# Placa_principal.net
KiCad netlist of a schematic drawn in EAGLE
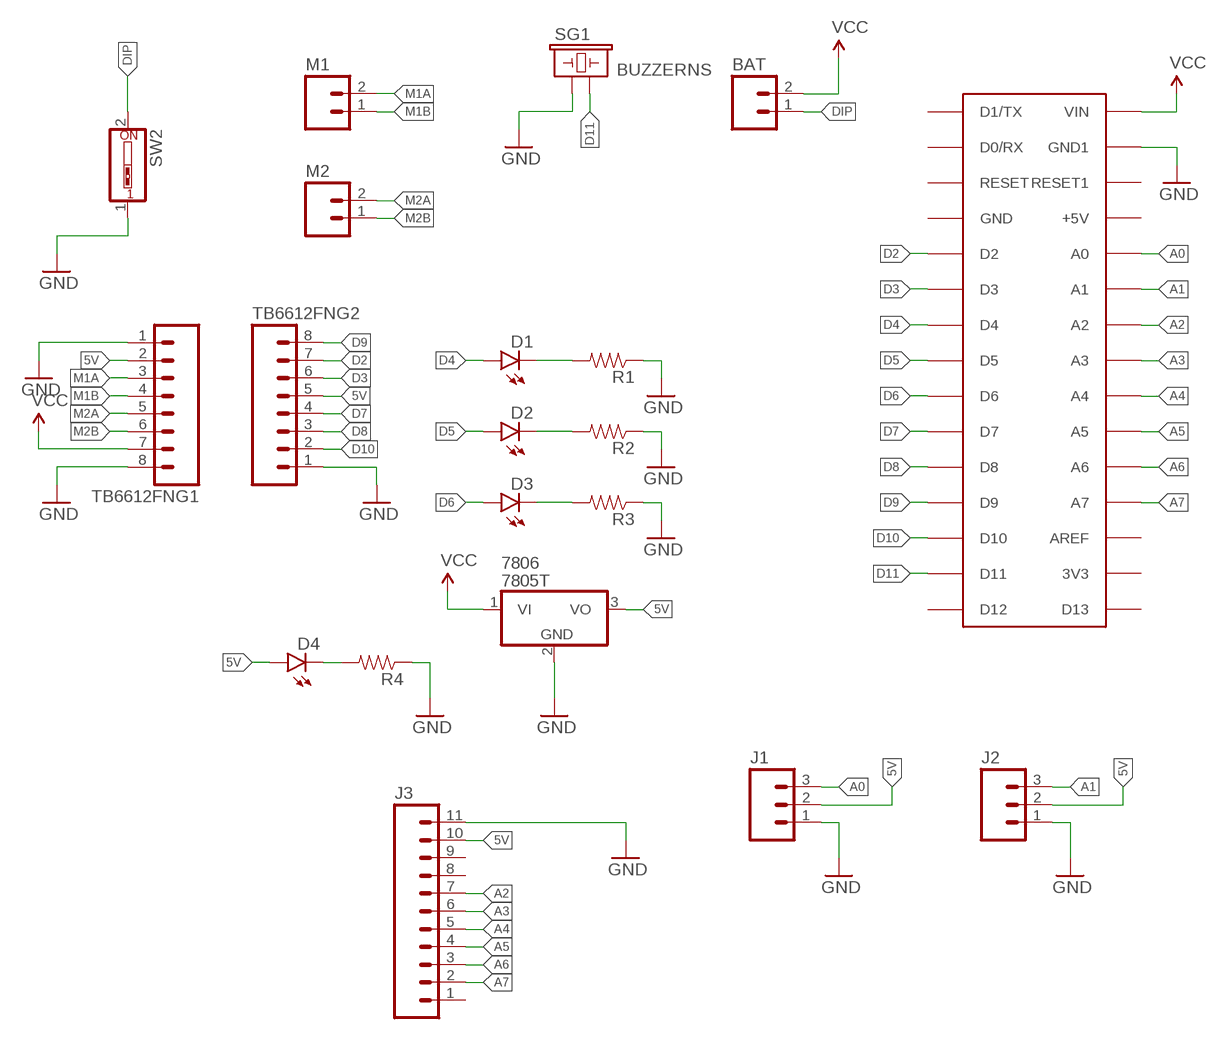
[diagram p0: schematic, sheet 1]

(export (version "E")
  (design (tool "Eeschema 10.0.6"))
  (components
    (comp (ref "7806")
      (value "7805T")
      (footprint "eagle-import:TO220H")
      (libsource (lib "eagle-import") (part "78T05"))
    )
    (comp (ref "BAT")
      (value "M02PTH")
      (footprint "eagle-import:1X02")
      (libsource (lib "eagle-import") (part "M02PTH"))
    )
    (comp (ref "D1")
      (value "LED5MM")
      (footprint "eagle-import:LED5MM")
      (libsource (lib "eagle-import") (part "LED5MM"))
    )
    (comp (ref "D2")
      (value "LED5MM")
      (footprint "eagle-import:LED5MM")
      (libsource (lib "eagle-import") (part "LED5MM"))
    )
    (comp (ref "D3")
      (value "LED5MM")
      (footprint "eagle-import:LED5MM")
      (libsource (lib "eagle-import") (part "LED5MM"))
    )
    (comp (ref "D4")
      (value "LED5MM")
      (footprint "eagle-import:LED5MM")
      (libsource (lib "eagle-import") (part "LED5MM"))
    )
    (comp (ref "J1")
      (value "M03PTH")
      (footprint "eagle-import:1X03")
      (libsource (lib "eagle-import") (part "M03PTH"))
    )
    (comp (ref "J2")
      (value "M03PTH")
      (footprint "eagle-import:1X03")
      (libsource (lib "eagle-import") (part "M03PTH"))
    )
    (comp (ref "J3")
      (value "M11PTH")
      (footprint "eagle-import:1X11")
      (libsource (lib "eagle-import") (part "M11PTH"))
    )
    (comp (ref "M1")
      (value "M02JST-PTH-VERT")
      (footprint "eagle-import:JST-2-PTH-VERT")
      (libsource (lib "eagle-import") (part "M02JST-PTH-VERT"))
    )
    (comp (ref "M2")
      (value "M02JST-PTH-VERT")
      (footprint "eagle-import:JST-2-PTH-VERT")
      (libsource (lib "eagle-import") (part "M02JST-PTH-VERT"))
    )
    (comp (ref "R1")
      (value "RESISTOREZ")
      (footprint "eagle-import:AXIAL-0.3EZ")
      (libsource (lib "eagle-import") (part "RESISTOREZ"))
    )
    (comp (ref "R2")
      (value "RESISTOREZ")
      (footprint "eagle-import:AXIAL-0.3EZ")
      (libsource (lib "eagle-import") (part "RESISTOREZ"))
    )
    (comp (ref "R3")
      (value "RESISTOREZ")
      (footprint "eagle-import:AXIAL-0.3EZ")
      (libsource (lib "eagle-import") (part "RESISTOREZ"))
    )
    (comp (ref "R4")
      (value "RESISTOREZ")
      (footprint "eagle-import:AXIAL-0.3EZ")
      (libsource (lib "eagle-import") (part "RESISTOREZ"))
    )
    (comp (ref "SG1")
      (value "BUZZERNS")
      (footprint "eagle-import:BUZZER-12MM-NS")
      (libsource (lib "eagle-import") (part "BUZZERNS"))
    )
    (comp (ref "SW2")
      (value "SW_DIP-1")
      (footprint "eagle-import:EDG-01")
      (libsource (lib "eagle-import") (part "SW_DIP-1"))
    )
    (comp (ref "TB6612FNG1")
      (value "M08")
      (footprint "eagle-import:1X08_ROUND")
      (libsource (lib "eagle-import") (part "M08"))
    )
    (comp (ref "TB6612FNG2")
      (value "M08")
      (footprint "eagle-import:1X08_ROUND")
      (libsource (lib "eagle-import") (part "M08"))
    )
    (comp (ref "U$2")
      (value "ARDUINONANO")
      (footprint "eagle-import:PDIP-32")
      (libsource (lib "eagle-import") (part "ARDUINONANO"))
    )
  )
  (nets
    (net (code "1") (name "5V") (class "Default")
      (node (ref "7806") (pin "3") (pinfunction "VO_3") (pintype "passive"))
      (node (ref "D4") (pin "A") (pinfunction "A_A") (pintype "passive"))
      (node (ref "J1") (pin "2") (pinfunction "2_2") (pintype "passive"))
      (node (ref "J2") (pin "2") (pinfunction "2_2") (pintype "passive"))
      (node (ref "J3") (pin "10") (pinfunction "10_10") (pintype "passive"))
      (node (ref "TB6612FNG1") (pin "2") (pinfunction "2_2") (pintype "passive"))
      (node (ref "TB6612FNG2") (pin "5") (pinfunction "5_5") (pintype "passive"))
    )
    (net (code "2") (name "A0") (class "Default")
      (node (ref "J1") (pin "3") (pinfunction "3_3") (pintype "passive"))
      (node (ref "U$2") (pin "A0") (pinfunction "A0_A0") (pintype "bidirectional"))
    )
    (net (code "3") (name "A1") (class "Default")
      (node (ref "J2") (pin "3") (pinfunction "3_3") (pintype "passive"))
      (node (ref "U$2") (pin "A1") (pinfunction "A1_A1") (pintype "bidirectional"))
    )
    (net (code "4") (name "A2") (class "Default")
      (node (ref "J3") (pin "7") (pinfunction "7_7") (pintype "passive"))
      (node (ref "U$2") (pin "A2") (pinfunction "A2_A2") (pintype "bidirectional"))
    )
    (net (code "5") (name "A3") (class "Default")
      (node (ref "J3") (pin "6") (pinfunction "6_6") (pintype "passive"))
      (node (ref "U$2") (pin "A3") (pinfunction "A3_A3") (pintype "bidirectional"))
    )
    (net (code "6") (name "A4") (class "Default")
      (node (ref "J3") (pin "5") (pinfunction "5_5") (pintype "passive"))
      (node (ref "U$2") (pin "A4") (pinfunction "A4_A4") (pintype "bidirectional"))
    )
    (net (code "7") (name "A5") (class "Default")
      (node (ref "J3") (pin "4") (pinfunction "4_4") (pintype "passive"))
      (node (ref "U$2") (pin "A5") (pinfunction "A5_A5") (pintype "bidirectional"))
    )
    (net (code "8") (name "A6") (class "Default")
      (node (ref "J3") (pin "3") (pinfunction "3_3") (pintype "passive"))
      (node (ref "U$2") (pin "A6") (pinfunction "A6_A6") (pintype "bidirectional"))
    )
    (net (code "9") (name "A7") (class "Default")
      (node (ref "J3") (pin "2") (pinfunction "2_2") (pintype "passive"))
      (node (ref "U$2") (pin "A7") (pinfunction "A7_A7") (pintype "bidirectional"))
    )
    (net (code "10") (name "D2") (class "Default")
      (node (ref "TB6612FNG2") (pin "7") (pinfunction "7_7") (pintype "passive"))
      (node (ref "U$2") (pin "D2") (pinfunction "D2_D2") (pintype "bidirectional"))
    )
    (net (code "11") (name "D3") (class "Default")
      (node (ref "TB6612FNG2") (pin "6") (pinfunction "6_6") (pintype "passive"))
      (node (ref "U$2") (pin "D3") (pinfunction "D3_D3") (pintype "bidirectional"))
    )
    (net (code "12") (name "D4") (class "Default")
      (node (ref "D1") (pin "A") (pinfunction "A_A") (pintype "passive"))
      (node (ref "U$2") (pin "D4") (pinfunction "D4_D4") (pintype "bidirectional"))
    )
    (net (code "13") (name "D5") (class "Default")
      (node (ref "D2") (pin "A") (pinfunction "A_A") (pintype "passive"))
      (node (ref "U$2") (pin "D5") (pinfunction "D5_D5") (pintype "bidirectional"))
    )
    (net (code "14") (name "D6") (class "Default")
      (node (ref "D3") (pin "A") (pinfunction "A_A") (pintype "passive"))
      (node (ref "U$2") (pin "D6") (pinfunction "D6_D6") (pintype "bidirectional"))
    )
    (net (code "15") (name "D7") (class "Default")
      (node (ref "TB6612FNG2") (pin "4") (pinfunction "4_4") (pintype "passive"))
      (node (ref "U$2") (pin "D7") (pinfunction "D7_D7") (pintype "bidirectional"))
    )
    (net (code "16") (name "D8") (class "Default")
      (node (ref "TB6612FNG2") (pin "3") (pinfunction "3_3") (pintype "passive"))
      (node (ref "U$2") (pin "D8") (pinfunction "D8_D8") (pintype "bidirectional"))
    )
    (net (code "17") (name "D9") (class "Default")
      (node (ref "TB6612FNG2") (pin "8") (pinfunction "8_8") (pintype "passive"))
      (node (ref "U$2") (pin "D9") (pinfunction "D9_D9") (pintype "bidirectional"))
    )
    (net (code "18") (name "D10") (class "Default")
      (node (ref "TB6612FNG2") (pin "2") (pinfunction "2_2") (pintype "passive"))
      (node (ref "U$2") (pin "D10") (pinfunction "D10_D10") (pintype "bidirectional"))
    )
    (net (code "19") (name "D11") (class "Default")
      (node (ref "SG1") (pin "-") (pinfunction "2_-") (pintype "passive"))
      (node (ref "U$2") (pin "D11") (pinfunction "D11_D11") (pintype "bidirectional"))
    )
    (net (code "20") (name "DIP") (class "Default")
      (node (ref "BAT") (pin "1") (pinfunction "1_1") (pintype "passive"))
      (node (ref "SW2") (pin "2") (pinfunction "2_2") (pintype "passive"))
    )
    (net (code "21") (name "GND") (class "Default")
      (node (ref "7806") (pin "2") (pinfunction "GND_2") (pintype "passive"))
      (node (ref "J1") (pin "1") (pinfunction "1_1") (pintype "passive"))
      (node (ref "J2") (pin "1") (pinfunction "1_1") (pintype "passive"))
      (node (ref "J3") (pin "11") (pinfunction "11_11") (pintype "passive"))
      (node (ref "R1") (pin "P$1") (pinfunction "1_P$1") (pintype "passive"))
      (node (ref "R2") (pin "P$1") (pinfunction "1_P$1") (pintype "passive"))
      (node (ref "R3") (pin "P$1") (pinfunction "1_P$1") (pintype "passive"))
      (node (ref "R4") (pin "P$1") (pinfunction "1_P$1") (pintype "passive"))
      (node (ref "SG1") (pin "+") (pinfunction "1_+") (pintype "passive"))
      (node (ref "SW2") (pin "1") (pinfunction "1_1") (pintype "passive"))
      (node (ref "TB6612FNG1") (pin "1") (pinfunction "1_1") (pintype "passive"))
      (node (ref "TB6612FNG1") (pin "8") (pinfunction "8_8") (pintype "passive"))
      (node (ref "TB6612FNG2") (pin "1") (pinfunction "1_1") (pintype "passive"))
      (node (ref "U$2") (pin "GND1") (pinfunction "GND1_GND1") (pintype "bidirectional"))
    )
    (net (code "22") (name "M1A") (class "Default")
      (node (ref "M1") (pin "2") (pinfunction "2_2") (pintype "passive"))
      (node (ref "TB6612FNG1") (pin "3") (pinfunction "3_3") (pintype "passive"))
    )
    (net (code "23") (name "M1B") (class "Default")
      (node (ref "M1") (pin "1") (pinfunction "1_1") (pintype "passive"))
      (node (ref "TB6612FNG1") (pin "4") (pinfunction "4_4") (pintype "passive"))
    )
    (net (code "24") (name "M2A") (class "Default")
      (node (ref "M2") (pin "2") (pinfunction "2_2") (pintype "passive"))
      (node (ref "TB6612FNG1") (pin "5") (pinfunction "5_5") (pintype "passive"))
    )
    (net (code "25") (name "M2B") (class "Default")
      (node (ref "M2") (pin "1") (pinfunction "1_1") (pintype "passive"))
      (node (ref "TB6612FNG1") (pin "6") (pinfunction "6_6") (pintype "passive"))
    )
    (net (code "26") (name "Net-(D1-C)") (class "Default")
      (node (ref "D1") (pin "K") (pinfunction "C_K") (pintype "passive"))
      (node (ref "R1") (pin "P$2") (pinfunction "2_P$2") (pintype "passive"))
    )
    (net (code "27") (name "Net-(D2-C)") (class "Default")
      (node (ref "D2") (pin "K") (pinfunction "C_K") (pintype "passive"))
      (node (ref "R2") (pin "P$2") (pinfunction "2_P$2") (pintype "passive"))
    )
    (net (code "28") (name "Net-(D3-C)") (class "Default")
      (node (ref "D3") (pin "K") (pinfunction "C_K") (pintype "passive"))
      (node (ref "R3") (pin "P$2") (pinfunction "2_P$2") (pintype "passive"))
    )
    (net (code "29") (name "Net-(D4-C)") (class "Default")
      (node (ref "D4") (pin "K") (pinfunction "C_K") (pintype "passive"))
      (node (ref "R4") (pin "P$2") (pinfunction "2_P$2") (pintype "passive"))
    )
    (net (code "30") (name "VCC") (class "Default")
      (node (ref "7806") (pin "1") (pinfunction "VI_1") (pintype "input"))
      (node (ref "BAT") (pin "2") (pinfunction "2_2") (pintype "passive"))
      (node (ref "TB6612FNG1") (pin "7") (pinfunction "7_7") (pintype "passive"))
      (node (ref "U$2") (pin "VIN") (pinfunction "VIN_VIN") (pintype "bidirectional"))
    )
    (net (code "31") (name "unconnected-(J3-Pad1)") (class "Default")
      (node (ref "J3") (pin "1") (pinfunction "1_1") (pintype "passive"))
    )
    (net (code "32") (name "unconnected-(J3-Pad8)") (class "Default")
      (node (ref "J3") (pin "8") (pinfunction "8_8") (pintype "passive"))
    )
    (net (code "33") (name "unconnected-(J3-Pad9)") (class "Default")
      (node (ref "J3") (pin "9") (pinfunction "9_9") (pintype "passive"))
    )
    (net (code "34") (name "unconnected-(U$2-Pad+5V)") (class "Default")
      (node (ref "U$2") (pin "+5V") (pinfunction "+5V_+5V") (pintype "bidirectional"))
    )
    (net (code "35") (name "unconnected-(U$2-Pad3V3)") (class "Default")
      (node (ref "U$2") (pin "3V3") (pinfunction "3V3_3V3") (pintype "bidirectional"))
    )
    (net (code "36") (name "unconnected-(U$2-PadAREF)") (class "Default")
      (node (ref "U$2") (pin "AREF") (pinfunction "AREF_AREF") (pintype "bidirectional"))
    )
    (net (code "37") (name "unconnected-(U$2-PadD0{slash}RX)") (class "Default")
      (node (ref "U$2") (pin "D0/RX") (pinfunction "D0/RX_D0/RX") (pintype "bidirectional"))
    )
    (net (code "38") (name "unconnected-(U$2-PadD1{slash}TX)") (class "Default")
      (node (ref "U$2") (pin "D1/TX") (pinfunction "D1/TX_D1/TX") (pintype "bidirectional"))
    )
    (net (code "39") (name "unconnected-(U$2-PadD12)") (class "Default")
      (node (ref "U$2") (pin "D12") (pinfunction "D12_D12") (pintype "bidirectional"))
    )
    (net (code "40") (name "unconnected-(U$2-PadD13)") (class "Default")
      (node (ref "U$2") (pin "D13") (pinfunction "D13_D13") (pintype "bidirectional"))
    )
    (net (code "41") (name "unconnected-(U$2-PadGND)") (class "Default")
      (node (ref "U$2") (pin "GND") (pinfunction "GND_GND") (pintype "bidirectional"))
    )
    (net (code "42") (name "unconnected-(U$2-PadRESET)") (class "Default")
      (node (ref "U$2") (pin "RESET") (pinfunction "RESET_RESET") (pintype "bidirectional"))
    )
    (net (code "43") (name "unconnected-(U$2-PadRESET1)") (class "Default")
      (node (ref "U$2") (pin "RESET1") (pinfunction "RESET1_RESET1") (pintype "bidirectional"))
    )
  )
)
